# Sheet1.net
KiCad netlist of a schematic drawn in Altium Designer
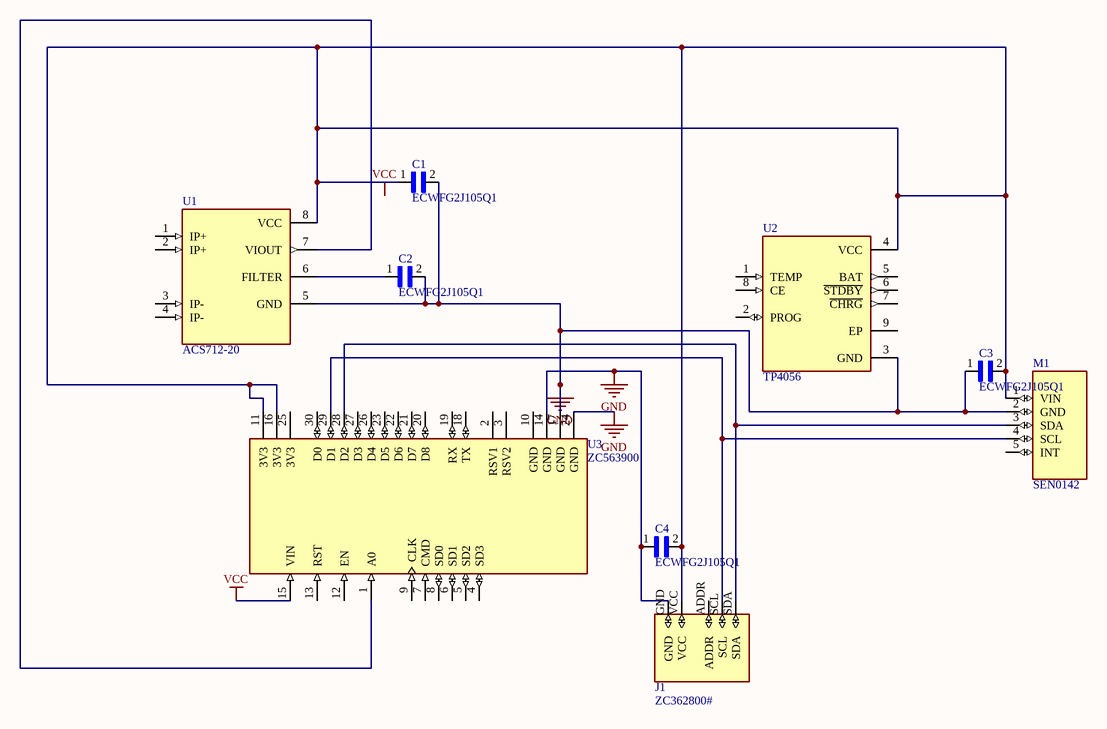
[diagram p0: Sheet1.SchDoc]

(export (version "E")
  (design (tool "Eeschema 10.0.6"))
  (components
    (comp (ref "C1")
      (value "ECWFG2J105Q1")
      (footprint "CAPRR2250W100L2700T1050H1900")
      (description "Metallized Polypropylene Film Capacitor")
      (fields (field (name "MF") "Panasonic"))
      (libsource (lib "ECWFG2J105Q1") (part "ECWFG2J105Q1"))
    )
    (comp (ref "C2")
      (value "ECWFG2J105Q1")
      (footprint "CAPRR2250W100L2700T1050H1900")
      (description "Metallized Polypropylene Film Capacitor")
      (fields (field (name "MF") "Panasonic"))
      (libsource (lib "ECWFG2J105Q1") (part "ECWFG2J105Q1"))
    )
    (comp (ref "C3")
      (value "ECWFG2J105Q1")
      (footprint "CAPRR2250W100L2700T1050H1900")
      (description "Metallized Polypropylene Film Capacitor")
      (fields (field (name "MF") "Panasonic"))
      (libsource (lib "ECWFG2J105Q1") (part "ECWFG2J105Q1"))
    )
    (comp (ref "C4")
      (value "ECWFG2J105Q1")
      (footprint "CAPRR2250W100L2700T1050H1900")
      (description "Metallized Polypropylene Film Capacitor")
      (fields (field (name "MF") "Panasonic"))
      (libsource (lib "ECWFG2J105Q1") (part "ECWFG2J105Q1"))
    )
    (comp (ref "J1")
      (value "ZC362800#")
      (footprint "ZC362800#")
      (description "1pc BH1750 Digital Ambient Light Intensity Sensor Module for Arduino GY-302")
      (fields (field (name "MF") "YKS"))
      (libsource (lib "ZC362800#") (part "ZC362800#"))
    )
    (comp (ref "M1")
      (value "SEN0142")
      (footprint "SEN0142")
      (description "MPU-6050 series Accelerometer, Gyroscope, 3 Axis Sensor Evaluation Board")
      (fields (field (name "MF") "DFRobot"))
      (libsource (lib "SEN0142") (part "SEN0142"))
    )
    (comp (ref "U1")
      (value "ACS712-20")
      (footprint "SOIC127P600X175-8N")
      (fields (field (name "MF") "Allegro MicroSystems"))
      (libsource (lib "ACS712-20") (part "ACS712-20"))
    )
    (comp (ref "U2")
      (value "TP4056")
      (footprint "SOP127P600X175-9N")
      (fields (field (name "MF") "others"))
      (libsource (lib "TP4056") (part "TP4056"))
    )
    (comp (ref "U3")
      (value "ZC563900")
      (footprint "MODULE_ZC563900")
      (description "NodeMcu Lua ESP8266 WIFI Internet of Things Network Development Module Board")
      (fields (field (name "MF") "YKS"))
      (libsource (lib "ZC563900") (part "ZC563900"))
    )
  )
  (nets
    (net (code "1") (name "GND") (class "Default")
      (node (ref "C1") (pin "2") (pinfunction "2_2") (pintype "passive"))
      (node (ref "C2") (pin "2") (pinfunction "2_2") (pintype "passive"))
      (node (ref "C3") (pin "1") (pinfunction "1_1") (pintype "passive"))
      (node (ref "C4") (pin "1") (pinfunction "1_1") (pintype "passive"))
      (node (ref "J1") (pin "GND") (pinfunction "GND_GND") (pintype "bidirectional"))
      (node (ref "M1") (pin "2") (pinfunction "GND_2") (pintype "bidirectional"))
      (node (ref "U1") (pin "5") (pinfunction "GND_5") (pintype "power_in"))
      (node (ref "U2") (pin "3") (pinfunction "GND_3") (pintype "power_in"))
      (node (ref "U3") (pin "14") (pinfunction "GND_14") (pintype "power_in"))
      (node (ref "U3") (pin "17") (pinfunction "GND_17") (pintype "power_in"))
      (node (ref "U3") (pin "24") (pinfunction "GND_24") (pintype "power_in"))
    )
    (net (code "2") (name "Net-(M1-SCL)") (class "Default")
      (node (ref "J1") (pin "SCL") (pinfunction "SCL_SCL") (pintype "bidirectional"))
      (node (ref "M1") (pin "4") (pinfunction "SCL_4") (pintype "bidirectional"))
      (node (ref "U3") (pin "29") (pinfunction "D1_29") (pintype "bidirectional"))
    )
    (net (code "3") (name "Net-(M1-SDA)") (class "Default")
      (node (ref "J1") (pin "SDA") (pinfunction "SDA_SDA") (pintype "bidirectional"))
      (node (ref "M1") (pin "3") (pinfunction "SDA_3") (pintype "bidirectional"))
      (node (ref "U3") (pin "28") (pinfunction "D2_28") (pintype "bidirectional"))
    )
    (net (code "4") (name "Net-(M1-VIN)") (class "Default")
      (node (ref "C1") (pin "1") (pinfunction "1_1") (pintype "passive"))
      (node (ref "C3") (pin "2") (pinfunction "2_2") (pintype "passive"))
      (node (ref "C4") (pin "2") (pinfunction "2_2") (pintype "passive"))
      (node (ref "J1") (pin "VCC") (pinfunction "VCC_VCC") (pintype "bidirectional"))
      (node (ref "M1") (pin "1") (pinfunction "VIN_1") (pintype "bidirectional"))
      (node (ref "U1") (pin "8") (pinfunction "VCC_8") (pintype "power_in"))
      (node (ref "U2") (pin "4") (pinfunction "VCC_4") (pintype "power_in"))
      (node (ref "U3") (pin "11") (pinfunction "3V3_11") (pintype "power_in"))
      (node (ref "U3") (pin "16") (pinfunction "3V3_16") (pintype "power_in"))
    )
    (net (code "5") (name "Net-(U1-FILTER)") (class "Default")
      (node (ref "C2") (pin "1") (pinfunction "1_1") (pintype "passive"))
      (node (ref "U1") (pin "6") (pinfunction "FILTER_6") (pintype "passive"))
    )
    (net (code "6") (name "Net-(U1-VIOUT)") (class "Default")
      (node (ref "U1") (pin "7") (pinfunction "VIOUT_7") (pintype "output"))
      (node (ref "U3") (pin "1") (pinfunction "A0_1") (pintype "input"))
    )
    (net (code "7") (name "VCC") (class "Default")
      (node (ref "U3") (pin "15") (pinfunction "VIN_15") (pintype "input"))
    )
    (net (code "8") (name "unconnected-(J1-PadADDR)") (class "Default")
      (node (ref "J1") (pin "ADDR") (pinfunction "ADDR_ADDR") (pintype "bidirectional"))
    )
    (net (code "9") (name "unconnected-(M1-INT-Pad5)") (class "Default")
      (node (ref "M1") (pin "5") (pinfunction "INT_5") (pintype "bidirectional"))
    )
    (net (code "10") (name "unconnected-(U1-IP+-Pad1)") (class "Default")
      (node (ref "U1") (pin "1") (pinfunction "IP+_1") (pintype "input"))
    )
    (net (code "11") (name "unconnected-(U1-IP+-Pad2)") (class "Default")
      (node (ref "U1") (pin "2") (pinfunction "IP+_2") (pintype "input"))
    )
    (net (code "12") (name "unconnected-(U1-IP--Pad3)") (class "Default")
      (node (ref "U1") (pin "3") (pinfunction "IP-_3") (pintype "input"))
    )
    (net (code "13") (name "unconnected-(U1-IP--Pad4)") (class "Default")
      (node (ref "U1") (pin "4") (pinfunction "IP-_4") (pintype "input"))
    )
    (net (code "14") (name "unconnected-(U2-BAT-Pad5)") (class "Default")
      (node (ref "U2") (pin "5") (pinfunction "BAT_5") (pintype "output"))
    )
    (net (code "15") (name "unconnected-(U2-CE-Pad8)") (class "Default")
      (node (ref "U2") (pin "8") (pinfunction "CE_8") (pintype "input"))
    )
    (net (code "16") (name "unconnected-(U2-EP-Pad9)") (class "Default")
      (node (ref "U2") (pin "9") (pinfunction "EP_9") (pintype "passive"))
    )
    (net (code "17") (name "unconnected-(U2-PROG-Pad2)") (class "Default")
      (node (ref "U2") (pin "2") (pinfunction "PROG_2") (pintype "bidirectional"))
    )
    (net (code "18") (name "unconnected-(U2-TEMP-Pad1)") (class "Default")
      (node (ref "U2") (pin "1") (pinfunction "TEMP_1") (pintype "input"))
    )
    (net (code "19") (name "unconnected-(U2-~{CHRG}-Pad7)") (class "Default")
      (node (ref "U2") (pin "7") (pinfunction "~{CHRG}_7") (pintype "output"))
    )
    (net (code "20") (name "unconnected-(U2-~{STDBY}-Pad6)") (class "Default")
      (node (ref "U2") (pin "6") (pinfunction "~{STDBY}_6") (pintype "output"))
    )
    (net (code "21") (name "unconnected-(U3-3V3-Pad25)") (class "Default")
      (node (ref "U3") (pin "25") (pinfunction "3V3_25") (pintype "power_in"))
    )
    (net (code "22") (name "unconnected-(U3-CLK-Pad9)") (class "Default")
      (node (ref "U3") (pin "9") (pinfunction "CLK_9") (pintype "input"))
    )
    (net (code "23") (name "unconnected-(U3-CMD-Pad7)") (class "Default")
      (node (ref "U3") (pin "7") (pinfunction "CMD_7") (pintype "input"))
    )
    (net (code "24") (name "unconnected-(U3-D0-Pad30)") (class "Default")
      (node (ref "U3") (pin "30") (pinfunction "D0_30") (pintype "bidirectional"))
    )
    (net (code "25") (name "unconnected-(U3-D3-Pad27)") (class "Default")
      (node (ref "U3") (pin "27") (pinfunction "D3_27") (pintype "bidirectional"))
    )
    (net (code "26") (name "unconnected-(U3-D4-Pad26)") (class "Default")
      (node (ref "U3") (pin "26") (pinfunction "D4_26") (pintype "bidirectional"))
    )
    (net (code "27") (name "unconnected-(U3-D5-Pad23)") (class "Default")
      (node (ref "U3") (pin "23") (pinfunction "D5_23") (pintype "bidirectional"))
    )
    (net (code "28") (name "unconnected-(U3-D6-Pad22)") (class "Default")
      (node (ref "U3") (pin "22") (pinfunction "D6_22") (pintype "bidirectional"))
    )
    (net (code "29") (name "unconnected-(U3-D7-Pad21)") (class "Default")
      (node (ref "U3") (pin "21") (pinfunction "D7_21") (pintype "bidirectional"))
    )
    (net (code "30") (name "unconnected-(U3-D8-Pad20)") (class "Default")
      (node (ref "U3") (pin "20") (pinfunction "D8_20") (pintype "bidirectional"))
    )
    (net (code "31") (name "unconnected-(U3-EN-Pad12)") (class "Default")
      (node (ref "U3") (pin "12") (pinfunction "EN_12") (pintype "input"))
    )
    (net (code "32") (name "unconnected-(U3-GND-Pad10)") (class "Default")
      (node (ref "U3") (pin "10") (pinfunction "GND_10") (pintype "power_in"))
    )
    (net (code "33") (name "unconnected-(U3-RST-Pad13)") (class "Default")
      (node (ref "U3") (pin "13") (pinfunction "RST_13") (pintype "input"))
    )
    (net (code "34") (name "unconnected-(U3-RSV1-Pad2)") (class "Default")
      (node (ref "U3") (pin "2") (pinfunction "RSV1_2") (pintype "passive"))
    )
    (net (code "35") (name "unconnected-(U3-RSV2-Pad3)") (class "Default")
      (node (ref "U3") (pin "3") (pinfunction "RSV2_3") (pintype "passive"))
    )
    (net (code "36") (name "unconnected-(U3-RX-Pad19)") (class "Default")
      (node (ref "U3") (pin "19") (pinfunction "RX_19") (pintype "bidirectional"))
    )
    (net (code "37") (name "unconnected-(U3-SD0-Pad8)") (class "Default")
      (node (ref "U3") (pin "8") (pinfunction "SD0_8") (pintype "bidirectional"))
    )
    (net (code "38") (name "unconnected-(U3-SD1-Pad6)") (class "Default")
      (node (ref "U3") (pin "6") (pinfunction "SD1_6") (pintype "bidirectional"))
    )
    (net (code "39") (name "unconnected-(U3-SD2-Pad5)") (class "Default")
      (node (ref "U3") (pin "5") (pinfunction "SD2_5") (pintype "bidirectional"))
    )
    (net (code "40") (name "unconnected-(U3-SD3-Pad4)") (class "Default")
      (node (ref "U3") (pin "4") (pinfunction "SD3_4") (pintype "bidirectional"))
    )
    (net (code "41") (name "unconnected-(U3-TX-Pad18)") (class "Default")
      (node (ref "U3") (pin "18") (pinfunction "TX_18") (pintype "bidirectional"))
    )
  )
)
